# M-Controller.net
KiCad netlist of a schematic drawn in EAGLE
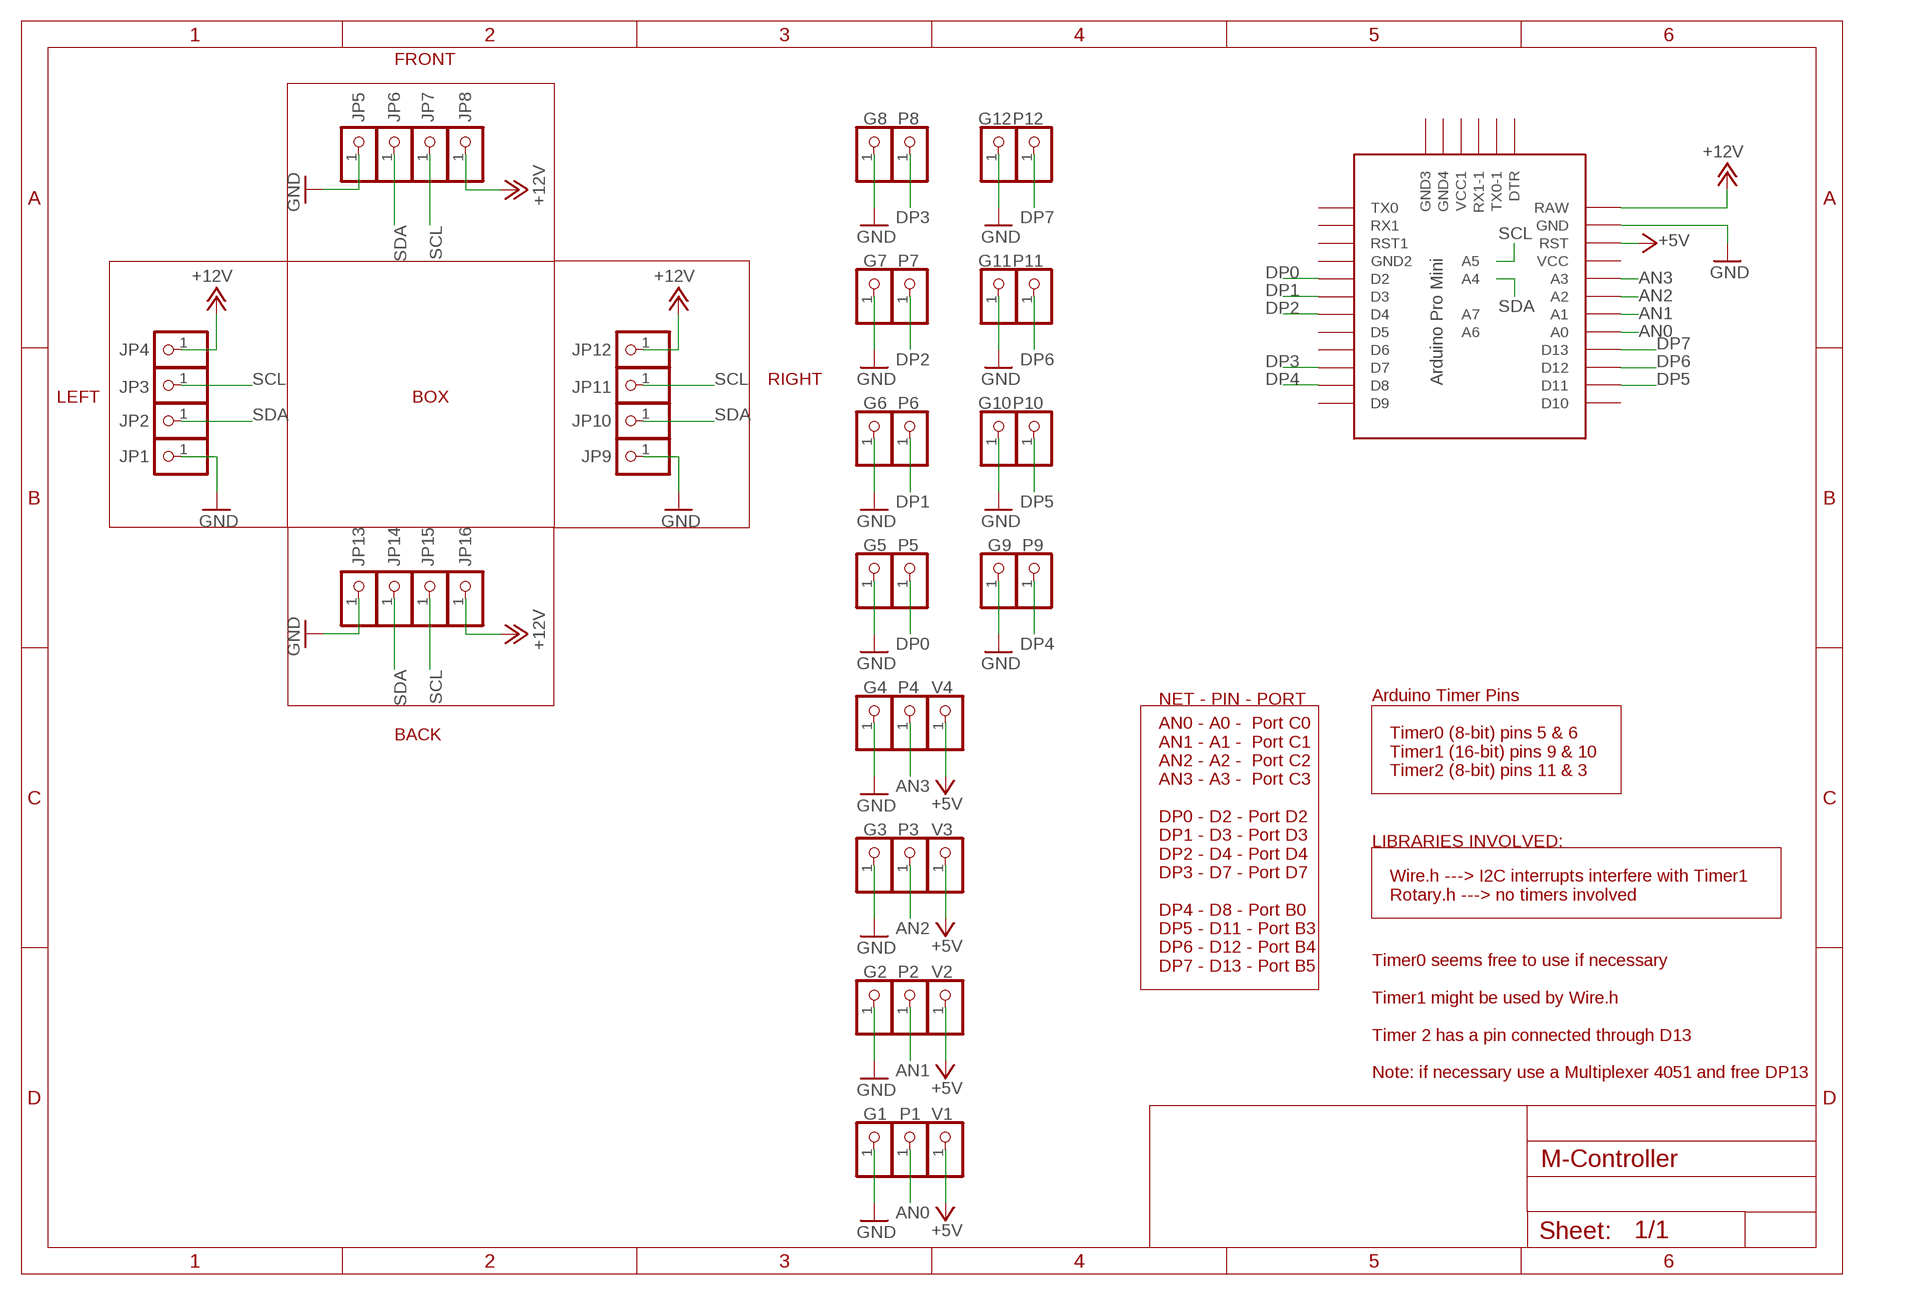
[diagram p0: schematic, sheet 1]

(export (version "E")
  (design (tool "Eeschema 10.0.6"))
  (components
    (comp (ref "G1")
      (value "PINHD-1X1")
      (footprint "eagle-import:1X01")
      (libsource (lib "eagle-import") (part "PINHD-1X1"))
    )
    (comp (ref "G2")
      (value "PINHD-1X1")
      (footprint "eagle-import:1X01")
      (libsource (lib "eagle-import") (part "PINHD-1X1"))
    )
    (comp (ref "G3")
      (value "PINHD-1X1")
      (footprint "eagle-import:1X01")
      (libsource (lib "eagle-import") (part "PINHD-1X1"))
    )
    (comp (ref "G4")
      (value "PINHD-1X1")
      (footprint "eagle-import:1X01")
      (libsource (lib "eagle-import") (part "PINHD-1X1"))
    )
    (comp (ref "G5")
      (value "PINHD-1X1")
      (footprint "eagle-import:1X01")
      (libsource (lib "eagle-import") (part "PINHD-1X1"))
    )
    (comp (ref "G6")
      (value "PINHD-1X1")
      (footprint "eagle-import:1X01")
      (libsource (lib "eagle-import") (part "PINHD-1X1"))
    )
    (comp (ref "G7")
      (value "PINHD-1X1")
      (footprint "eagle-import:1X01")
      (libsource (lib "eagle-import") (part "PINHD-1X1"))
    )
    (comp (ref "G8")
      (value "PINHD-1X1")
      (footprint "eagle-import:1X01")
      (libsource (lib "eagle-import") (part "PINHD-1X1"))
    )
    (comp (ref "G9")
      (value "PINHD-1X1")
      (footprint "eagle-import:1X01")
      (libsource (lib "eagle-import") (part "PINHD-1X1"))
    )
    (comp (ref "G10")
      (value "PINHD-1X1")
      (footprint "eagle-import:1X01")
      (libsource (lib "eagle-import") (part "PINHD-1X1"))
    )
    (comp (ref "G11")
      (value "PINHD-1X1")
      (footprint "eagle-import:1X01")
      (libsource (lib "eagle-import") (part "PINHD-1X1"))
    )
    (comp (ref "G12")
      (value "PINHD-1X1")
      (footprint "eagle-import:1X01")
      (libsource (lib "eagle-import") (part "PINHD-1X1"))
    )
    (comp (ref "JP1")
      (value "PINHD-1X1")
      (footprint "eagle-import:1X01")
      (libsource (lib "eagle-import") (part "PINHD-1X1"))
    )
    (comp (ref "JP2")
      (value "PINHD-1X1")
      (footprint "eagle-import:1X01")
      (libsource (lib "eagle-import") (part "PINHD-1X1"))
    )
    (comp (ref "JP3")
      (value "PINHD-1X1")
      (footprint "eagle-import:1X01")
      (libsource (lib "eagle-import") (part "PINHD-1X1"))
    )
    (comp (ref "JP4")
      (value "PINHD-1X1")
      (footprint "eagle-import:1X01")
      (libsource (lib "eagle-import") (part "PINHD-1X1"))
    )
    (comp (ref "JP5")
      (value "PINHD-1X1")
      (footprint "eagle-import:1X01")
      (libsource (lib "eagle-import") (part "PINHD-1X1"))
    )
    (comp (ref "JP6")
      (value "PINHD-1X1")
      (footprint "eagle-import:1X01")
      (libsource (lib "eagle-import") (part "PINHD-1X1"))
    )
    (comp (ref "JP7")
      (value "PINHD-1X1")
      (footprint "eagle-import:1X01")
      (libsource (lib "eagle-import") (part "PINHD-1X1"))
    )
    (comp (ref "JP8")
      (value "PINHD-1X1")
      (footprint "eagle-import:1X01")
      (libsource (lib "eagle-import") (part "PINHD-1X1"))
    )
    (comp (ref "JP9")
      (value "PINHD-1X1")
      (footprint "eagle-import:1X01")
      (libsource (lib "eagle-import") (part "PINHD-1X1"))
    )
    (comp (ref "JP10")
      (value "PINHD-1X1")
      (footprint "eagle-import:1X01")
      (libsource (lib "eagle-import") (part "PINHD-1X1"))
    )
    (comp (ref "JP11")
      (value "PINHD-1X1")
      (footprint "eagle-import:1X01")
      (libsource (lib "eagle-import") (part "PINHD-1X1"))
    )
    (comp (ref "JP12")
      (value "PINHD-1X1")
      (footprint "eagle-import:1X01")
      (libsource (lib "eagle-import") (part "PINHD-1X1"))
    )
    (comp (ref "JP13")
      (value "PINHD-1X1")
      (footprint "eagle-import:1X01")
      (libsource (lib "eagle-import") (part "PINHD-1X1"))
    )
    (comp (ref "JP14")
      (value "PINHD-1X1")
      (footprint "eagle-import:1X01")
      (libsource (lib "eagle-import") (part "PINHD-1X1"))
    )
    (comp (ref "JP15")
      (value "PINHD-1X1")
      (footprint "eagle-import:1X01")
      (libsource (lib "eagle-import") (part "PINHD-1X1"))
    )
    (comp (ref "JP16")
      (value "PINHD-1X1")
      (footprint "eagle-import:1X01")
      (libsource (lib "eagle-import") (part "PINHD-1X1"))
    )
    (comp (ref "P1")
      (value "PINHD-1X1")
      (footprint "eagle-import:1X01")
      (libsource (lib "eagle-import") (part "PINHD-1X1"))
    )
    (comp (ref "P2")
      (value "PINHD-1X1")
      (footprint "eagle-import:1X01")
      (libsource (lib "eagle-import") (part "PINHD-1X1"))
    )
    (comp (ref "P3")
      (value "PINHD-1X1")
      (footprint "eagle-import:1X01")
      (libsource (lib "eagle-import") (part "PINHD-1X1"))
    )
    (comp (ref "P4")
      (value "PINHD-1X1")
      (footprint "eagle-import:1X01")
      (libsource (lib "eagle-import") (part "PINHD-1X1"))
    )
    (comp (ref "P5")
      (value "PINHD-1X1")
      (footprint "eagle-import:1X01")
      (libsource (lib "eagle-import") (part "PINHD-1X1"))
    )
    (comp (ref "P6")
      (value "PINHD-1X1")
      (footprint "eagle-import:1X01")
      (libsource (lib "eagle-import") (part "PINHD-1X1"))
    )
    (comp (ref "P7")
      (value "PINHD-1X1")
      (footprint "eagle-import:1X01")
      (libsource (lib "eagle-import") (part "PINHD-1X1"))
    )
    (comp (ref "P8")
      (value "PINHD-1X1")
      (footprint "eagle-import:1X01")
      (libsource (lib "eagle-import") (part "PINHD-1X1"))
    )
    (comp (ref "P9")
      (value "PINHD-1X1")
      (footprint "eagle-import:1X01")
      (libsource (lib "eagle-import") (part "PINHD-1X1"))
    )
    (comp (ref "P10")
      (value "PINHD-1X1")
      (footprint "eagle-import:1X01")
      (libsource (lib "eagle-import") (part "PINHD-1X1"))
    )
    (comp (ref "P11")
      (value "PINHD-1X1")
      (footprint "eagle-import:1X01")
      (libsource (lib "eagle-import") (part "PINHD-1X1"))
    )
    (comp (ref "P12")
      (value "PINHD-1X1")
      (footprint "eagle-import:1X01")
      (libsource (lib "eagle-import") (part "PINHD-1X1"))
    )
    (comp (ref "U$1")
      (value "PRO-MINI-2")
      (footprint "eagle-import:PRO-MINI-2")
      (libsource (lib "eagle-import") (part "PRO-MINI-2"))
    )
    (comp (ref "V1")
      (value "PINHD-1X1")
      (footprint "eagle-import:1X01")
      (libsource (lib "eagle-import") (part "PINHD-1X1"))
    )
    (comp (ref "V2")
      (value "PINHD-1X1")
      (footprint "eagle-import:1X01")
      (libsource (lib "eagle-import") (part "PINHD-1X1"))
    )
    (comp (ref "V3")
      (value "PINHD-1X1")
      (footprint "eagle-import:1X01")
      (libsource (lib "eagle-import") (part "PINHD-1X1"))
    )
    (comp (ref "V4")
      (value "PINHD-1X1")
      (footprint "eagle-import:1X01")
      (libsource (lib "eagle-import") (part "PINHD-1X1"))
    )
  )
  (nets
    (net (code "1") (name "+5V") (class "Default")
      (node (ref "U$1") (pin "RST") (pinfunction "RST_RST") (pintype "bidirectional"))
      (node (ref "V1") (pin "1") (pinfunction "1_1") (pintype "passive"))
      (node (ref "V2") (pin "1") (pinfunction "1_1") (pintype "passive"))
      (node (ref "V3") (pin "1") (pinfunction "1_1") (pintype "passive"))
      (node (ref "V4") (pin "1") (pinfunction "1_1") (pintype "passive"))
    )
    (net (code "2") (name "+12V") (class "Default")
      (node (ref "JP12") (pin "1") (pinfunction "1_1") (pintype "passive"))
      (node (ref "JP16") (pin "1") (pinfunction "1_1") (pintype "passive"))
      (node (ref "JP4") (pin "1") (pinfunction "1_1") (pintype "passive"))
      (node (ref "JP8") (pin "1") (pinfunction "1_1") (pintype "passive"))
      (node (ref "U$1") (pin "RAW") (pinfunction "RAW_RAW") (pintype "bidirectional"))
    )
    (net (code "3") (name "/AN0") (class "Default")
      (node (ref "P1") (pin "1") (pinfunction "1_1") (pintype "passive"))
      (node (ref "U$1") (pin "A0") (pinfunction "A0_A0") (pintype "bidirectional"))
    )
    (net (code "4") (name "/AN1") (class "Default")
      (node (ref "P2") (pin "1") (pinfunction "1_1") (pintype "passive"))
      (node (ref "U$1") (pin "A1") (pinfunction "A1_A1") (pintype "bidirectional"))
    )
    (net (code "5") (name "/AN2") (class "Default")
      (node (ref "P3") (pin "1") (pinfunction "1_1") (pintype "passive"))
      (node (ref "U$1") (pin "A2") (pinfunction "A2_A2") (pintype "bidirectional"))
    )
    (net (code "6") (name "/AN3") (class "Default")
      (node (ref "P4") (pin "1") (pinfunction "1_1") (pintype "passive"))
      (node (ref "U$1") (pin "A3") (pinfunction "A3_A3") (pintype "bidirectional"))
    )
    (net (code "7") (name "/DP0") (class "Default")
      (node (ref "P5") (pin "1") (pinfunction "1_1") (pintype "passive"))
      (node (ref "U$1") (pin "D2") (pinfunction "D2_D2") (pintype "bidirectional"))
    )
    (net (code "8") (name "/DP1") (class "Default")
      (node (ref "P6") (pin "1") (pinfunction "1_1") (pintype "passive"))
      (node (ref "U$1") (pin "D3") (pinfunction "D3_D3") (pintype "bidirectional"))
    )
    (net (code "9") (name "/DP2") (class "Default")
      (node (ref "P7") (pin "1") (pinfunction "1_1") (pintype "passive"))
      (node (ref "U$1") (pin "D4") (pinfunction "D4_D4") (pintype "bidirectional"))
    )
    (net (code "10") (name "/DP3") (class "Default")
      (node (ref "P8") (pin "1") (pinfunction "1_1") (pintype "passive"))
      (node (ref "U$1") (pin "D7") (pinfunction "D7_D7") (pintype "bidirectional"))
    )
    (net (code "11") (name "/DP4") (class "Default")
      (node (ref "P9") (pin "1") (pinfunction "1_1") (pintype "passive"))
      (node (ref "U$1") (pin "D8") (pinfunction "D8_D8") (pintype "bidirectional"))
    )
    (net (code "12") (name "/DP5") (class "Default")
      (node (ref "P10") (pin "1") (pinfunction "1_1") (pintype "passive"))
      (node (ref "U$1") (pin "D11") (pinfunction "D11_D11") (pintype "bidirectional"))
    )
    (net (code "13") (name "/DP6") (class "Default")
      (node (ref "P11") (pin "1") (pinfunction "1_1") (pintype "passive"))
      (node (ref "U$1") (pin "D12") (pinfunction "D12_D12") (pintype "bidirectional"))
    )
    (net (code "14") (name "/DP7") (class "Default")
      (node (ref "P12") (pin "1") (pinfunction "1_1") (pintype "passive"))
      (node (ref "U$1") (pin "D13") (pinfunction "D13_D13") (pintype "bidirectional"))
    )
    (net (code "15") (name "/SCL") (class "Default")
      (node (ref "JP11") (pin "1") (pinfunction "1_1") (pintype "passive"))
      (node (ref "JP15") (pin "1") (pinfunction "1_1") (pintype "passive"))
      (node (ref "JP3") (pin "1") (pinfunction "1_1") (pintype "passive"))
      (node (ref "JP7") (pin "1") (pinfunction "1_1") (pintype "passive"))
      (node (ref "U$1") (pin "A5") (pinfunction "A5_A5") (pintype "bidirectional"))
    )
    (net (code "16") (name "/SDA") (class "Default")
      (node (ref "JP10") (pin "1") (pinfunction "1_1") (pintype "passive"))
      (node (ref "JP14") (pin "1") (pinfunction "1_1") (pintype "passive"))
      (node (ref "JP2") (pin "1") (pinfunction "1_1") (pintype "passive"))
      (node (ref "JP6") (pin "1") (pinfunction "1_1") (pintype "passive"))
      (node (ref "U$1") (pin "A4") (pinfunction "A4_A4") (pintype "bidirectional"))
    )
    (net (code "17") (name "GND") (class "Default")
      (node (ref "G1") (pin "1") (pinfunction "1_1") (pintype "passive"))
      (node (ref "G10") (pin "1") (pinfunction "1_1") (pintype "passive"))
      (node (ref "G11") (pin "1") (pinfunction "1_1") (pintype "passive"))
      (node (ref "G12") (pin "1") (pinfunction "1_1") (pintype "passive"))
      (node (ref "G2") (pin "1") (pinfunction "1_1") (pintype "passive"))
      (node (ref "G3") (pin "1") (pinfunction "1_1") (pintype "passive"))
      (node (ref "G4") (pin "1") (pinfunction "1_1") (pintype "passive"))
      (node (ref "G5") (pin "1") (pinfunction "1_1") (pintype "passive"))
      (node (ref "G6") (pin "1") (pinfunction "1_1") (pintype "passive"))
      (node (ref "G7") (pin "1") (pinfunction "1_1") (pintype "passive"))
      (node (ref "G8") (pin "1") (pinfunction "1_1") (pintype "passive"))
      (node (ref "G9") (pin "1") (pinfunction "1_1") (pintype "passive"))
      (node (ref "JP1") (pin "1") (pinfunction "1_1") (pintype "passive"))
      (node (ref "JP13") (pin "1") (pinfunction "1_1") (pintype "passive"))
      (node (ref "JP5") (pin "1") (pinfunction "1_1") (pintype "passive"))
      (node (ref "JP9") (pin "1") (pinfunction "1_1") (pintype "passive"))
      (node (ref "U$1") (pin "GND") (pinfunction "GND_GND") (pintype "bidirectional"))
    )
    (net (code "18") (name "unconnected-(U$1-GND2-PadGND1)") (class "Default")
      (node (ref "U$1") (pin "GND1") (pinfunction "GND2_GND1") (pintype "bidirectional"))
    )
    (net (code "19") (name "unconnected-(U$1-GND3-PadGND2)") (class "Default")
      (node (ref "U$1") (pin "GND2") (pinfunction "GND3_GND2") (pintype "bidirectional"))
    )
    (net (code "20") (name "unconnected-(U$1-GND4-PadGND3)") (class "Default")
      (node (ref "U$1") (pin "GND3") (pinfunction "GND4_GND3") (pintype "bidirectional"))
    )
    (net (code "21") (name "unconnected-(U$1-PadA6)") (class "Default")
      (node (ref "U$1") (pin "A6") (pinfunction "A6_A6") (pintype "bidirectional"))
    )
    (net (code "22") (name "unconnected-(U$1-PadA7)") (class "Default")
      (node (ref "U$1") (pin "A7") (pinfunction "A7_A7") (pintype "bidirectional"))
    )
    (net (code "23") (name "unconnected-(U$1-PadD5)") (class "Default")
      (node (ref "U$1") (pin "D5") (pinfunction "D5_D5") (pintype "bidirectional"))
    )
    (net (code "24") (name "unconnected-(U$1-PadD6)") (class "Default")
      (node (ref "U$1") (pin "D6") (pinfunction "D6_D6") (pintype "bidirectional"))
    )
    (net (code "25") (name "unconnected-(U$1-PadD9)") (class "Default")
      (node (ref "U$1") (pin "D9") (pinfunction "D9_D9") (pintype "bidirectional"))
    )
    (net (code "26") (name "unconnected-(U$1-PadD10)") (class "Default")
      (node (ref "U$1") (pin "D10") (pinfunction "D10_D10") (pintype "bidirectional"))
    )
    (net (code "27") (name "unconnected-(U$1-PadDTR)") (class "Default")
      (node (ref "U$1") (pin "DTR") (pinfunction "DTR_DTR") (pintype "bidirectional"))
    )
    (net (code "28") (name "unconnected-(U$1-PadRST1)") (class "Default")
      (node (ref "U$1") (pin "RST1") (pinfunction "RST1_RST1") (pintype "bidirectional"))
    )
    (net (code "29") (name "unconnected-(U$1-PadRX1)") (class "Default")
      (node (ref "U$1") (pin "RX1") (pinfunction "RX1_RX1") (pintype "bidirectional"))
    )
    (net (code "30") (name "unconnected-(U$1-PadRX1-1)") (class "Default")
      (node (ref "U$1") (pin "RX1-1") (pinfunction "RX1-1_RX1-1") (pintype "bidirectional"))
    )
    (net (code "31") (name "unconnected-(U$1-PadTX0)") (class "Default")
      (node (ref "U$1") (pin "TX0") (pinfunction "TX0_TX0") (pintype "bidirectional"))
    )
    (net (code "32") (name "unconnected-(U$1-PadTX0-1)") (class "Default")
      (node (ref "U$1") (pin "TX0-1") (pinfunction "TX0-1_TX0-1") (pintype "bidirectional"))
    )
    (net (code "33") (name "unconnected-(U$1-PadVCC)") (class "Default")
      (node (ref "U$1") (pin "VCC") (pinfunction "VCC_VCC") (pintype "bidirectional"))
    )
    (net (code "34") (name "unconnected-(U$1-PadVCC1)") (class "Default")
      (node (ref "U$1") (pin "VCC1") (pinfunction "VCC1_VCC1") (pintype "bidirectional"))
    )
  )
)
